# 1-Schematic_bmi160-tester.net
KiCad netlist of a schematic drawn in EasyEDA
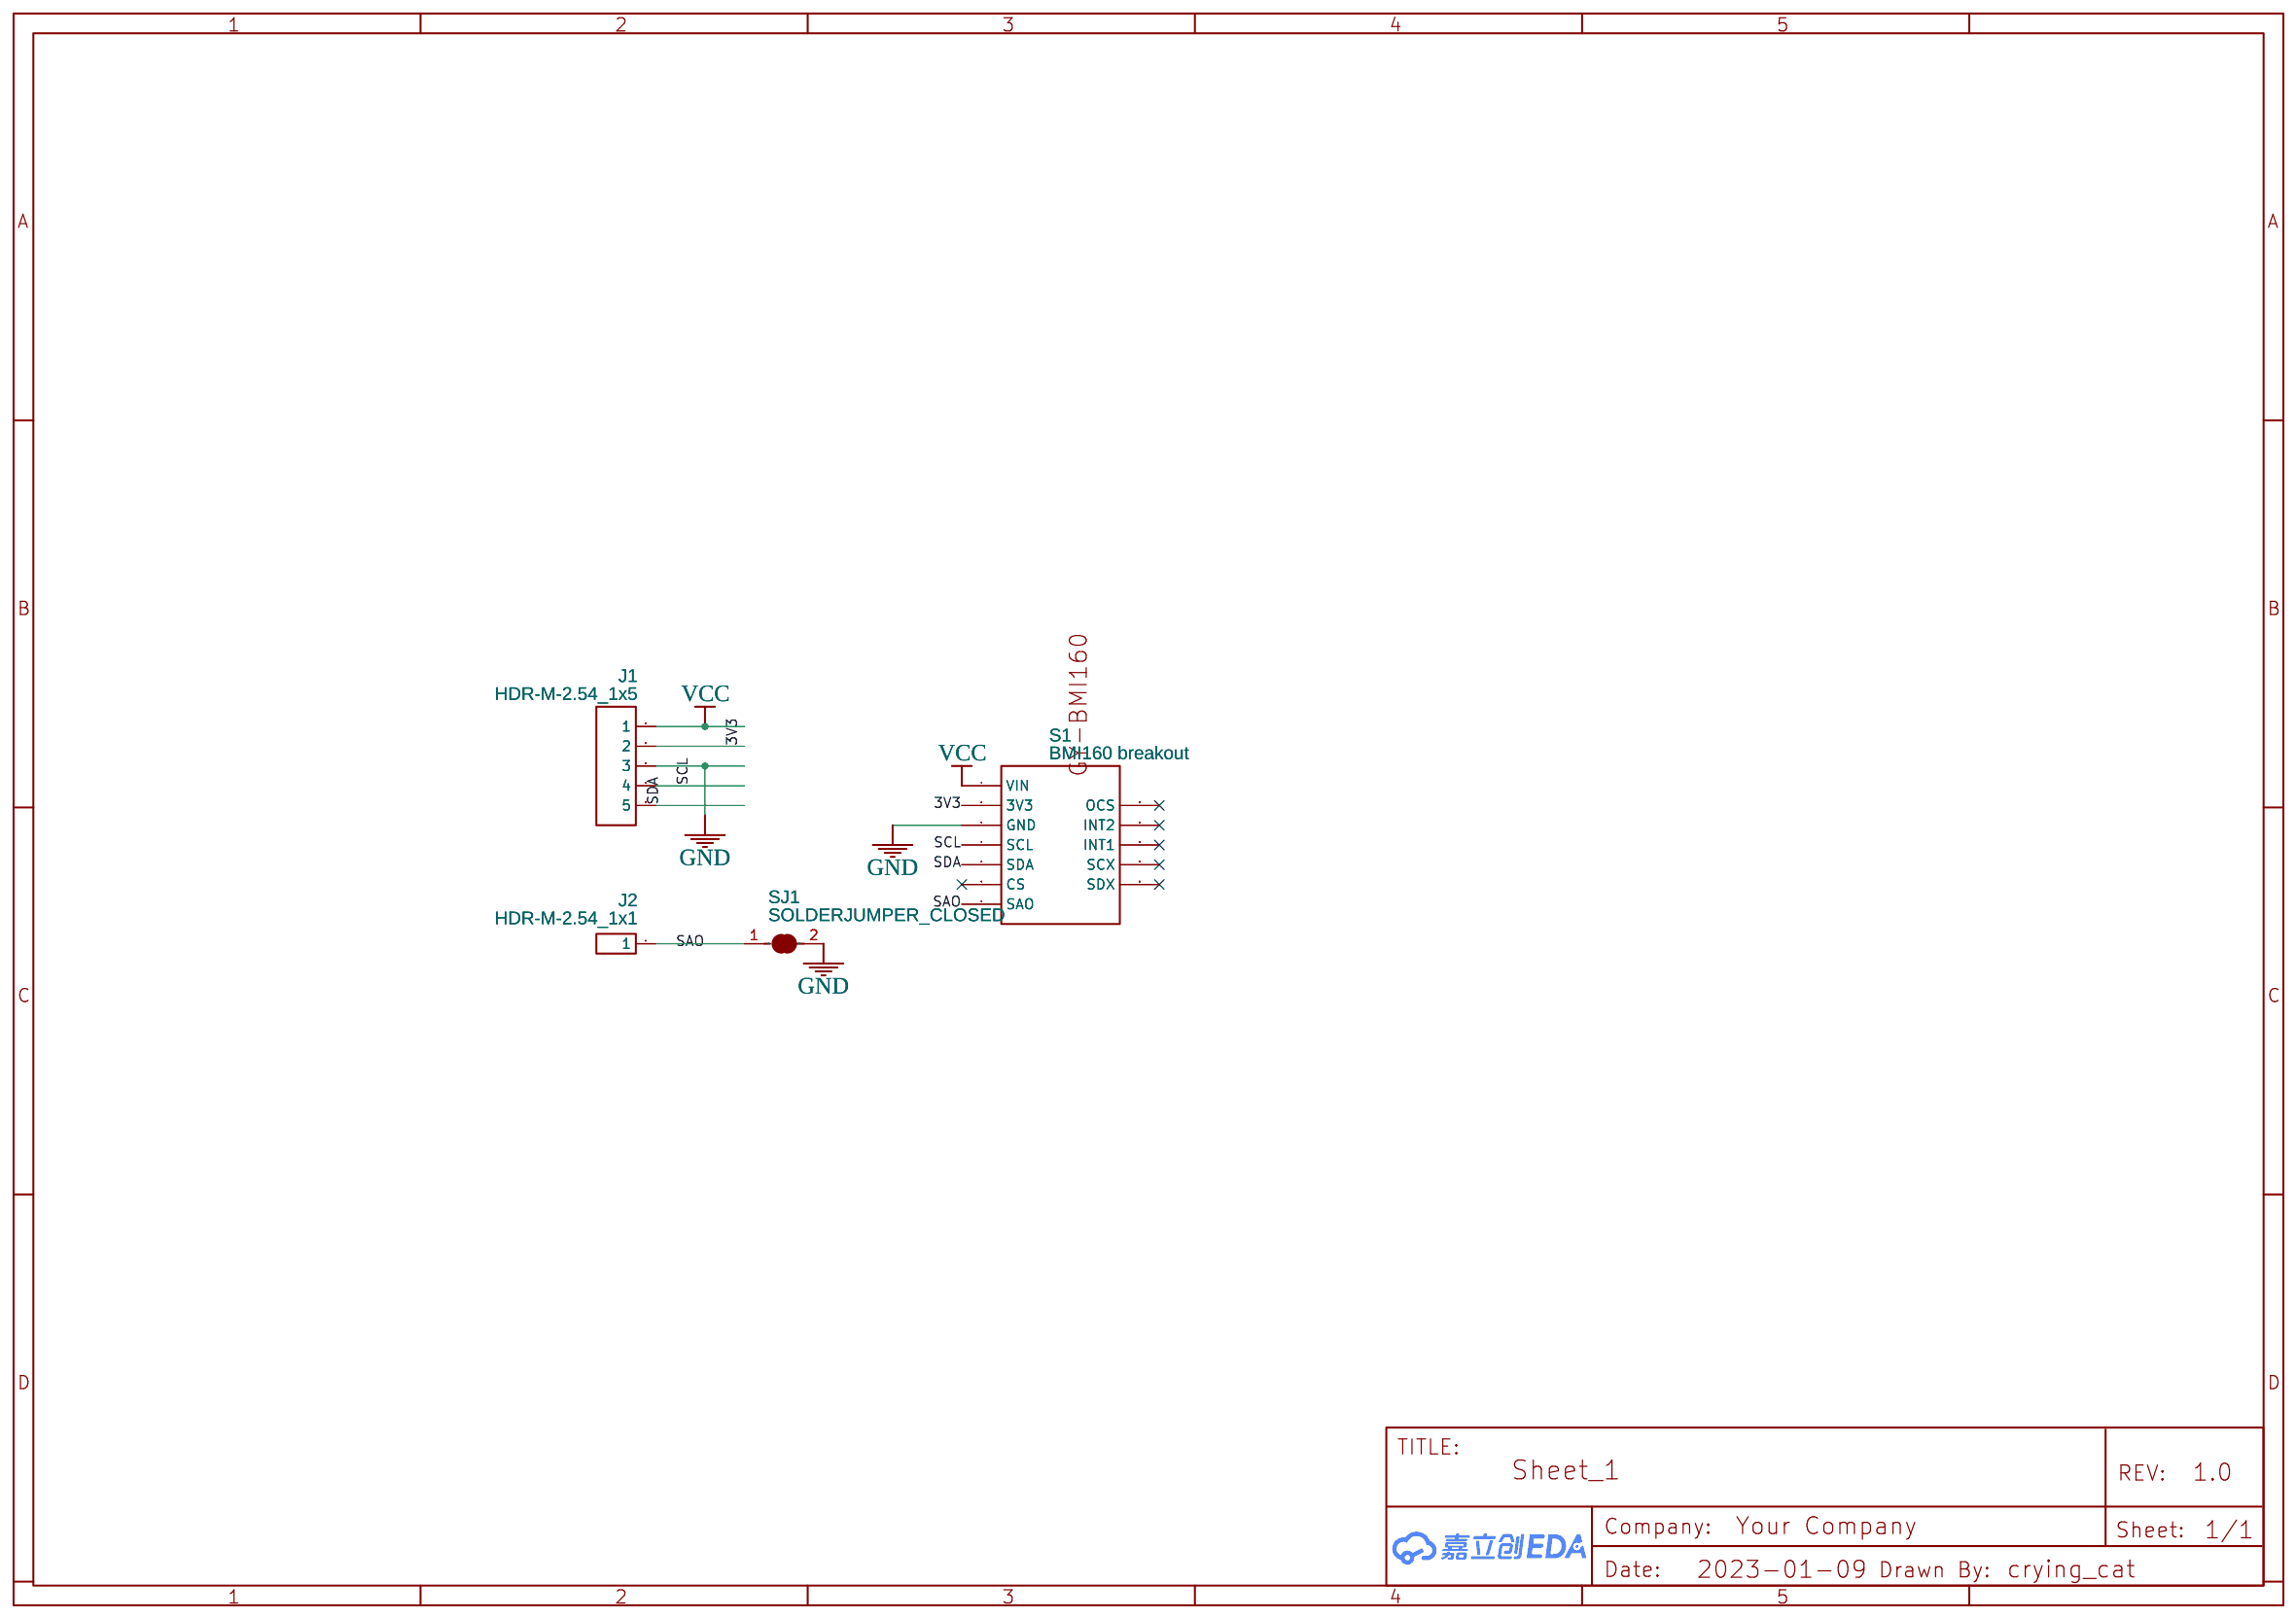
[diagram p0: schematic sheet]

(export (version "E")
  (design (tool "Eeschema 10.0.6"))
  (components
    (comp (ref "J1")
      (value "HDR-M-2.54_1x5")
      (fields (field (name "BOM_Supplier Part") "C358687"))
      (libsource (lib "") (part "HDR-M-2.54_1x5"))
    )
    (comp (ref "J2")
      (value "HDR-M-2.54_1x1")
      (fields (field (name "BOM_Supplier Part") "C81276"))
      (libsource (lib "") (part "HDR-M-2.54_1x1"))
    )
    (comp (ref "S1") (value "BMI160 breakout") (libsource (lib "") (part "BMI160 breakout")))
    (comp (ref "SJ1") (value "SOLDERJUMPER_CLOSED") (libsource (lib "") (part "SOLDERJUMPER_CLOSED")))
  )
  (nets
    (net (code "1") (name "/3V3") (class "Default")
      (node (ref "J1") (pin "2") (pinfunction "2_2") (pintype "unspecified"))
      (node (ref "S1") (pin "6") (pinfunction "3V3_6") (pintype "unspecified"))
    )
    (net (code "2") (name "/SAO") (class "Default")
      (node (ref "J2") (pin "1") (pinfunction "1_1") (pintype "input"))
      (node (ref "S1") (pin "1") (pinfunction "SAO_1") (pintype "unspecified"))
      (node (ref "SJ1") (pin "1") (pinfunction "1_1") (pintype "bidirectional"))
    )
    (net (code "3") (name "/SCL") (class "Default")
      (node (ref "J1") (pin "4") (pinfunction "4_4") (pintype "unspecified"))
      (node (ref "S1") (pin "4") (pinfunction "SCL_4") (pintype "unspecified"))
    )
    (net (code "4") (name "/SDA") (class "Default")
      (node (ref "J1") (pin "5") (pinfunction "5_5") (pintype "unspecified"))
      (node (ref "S1") (pin "3") (pinfunction "SDA_3") (pintype "unspecified"))
    )
    (net (code "5") (name "GND") (class "Default")
      (node (ref "J1") (pin "3") (pinfunction "3_3") (pintype "unspecified"))
      (node (ref "S1") (pin "5") (pinfunction "GND_5") (pintype "unspecified"))
      (node (ref "SJ1") (pin "2") (pinfunction "2_2") (pintype "bidirectional"))
    )
    (net (code "6") (name "VCC") (class "Default")
      (node (ref "J1") (pin "1") (pinfunction "1_1") (pintype "unspecified"))
      (node (ref "S1") (pin "7") (pinfunction "VIN_7") (pintype "unspecified"))
    )
    (net (code "7") (name "unconnected-(S1-CS-Pad2)") (class "Default")
      (node (ref "S1") (pin "2") (pinfunction "CS_2") (pintype "unspecified+no_connect"))
    )
    (net (code "8") (name "unconnected-(S1-INT1-Pad10)") (class "Default")
      (node (ref "S1") (pin "10") (pinfunction "INT1_10") (pintype "unspecified+no_connect"))
    )
    (net (code "9") (name "unconnected-(S1-INT2-Pad9)") (class "Default")
      (node (ref "S1") (pin "9") (pinfunction "INT2_9") (pintype "unspecified+no_connect"))
    )
    (net (code "10") (name "unconnected-(S1-OCS-Pad8)") (class "Default")
      (node (ref "S1") (pin "8") (pinfunction "OCS_8") (pintype "unspecified+no_connect"))
    )
    (net (code "11") (name "unconnected-(S1-SCX-Pad11)") (class "Default")
      (node (ref "S1") (pin "11") (pinfunction "SCX_11") (pintype "unspecified+no_connect"))
    )
    (net (code "12") (name "unconnected-(S1-SDX-Pad12)") (class "Default")
      (node (ref "S1") (pin "12") (pinfunction "SDX_12") (pintype "unspecified+no_connect"))
    )
  )
)
